# 2_MCU_schdoc.net
KiCad netlist of a schematic drawn in Altium Designer
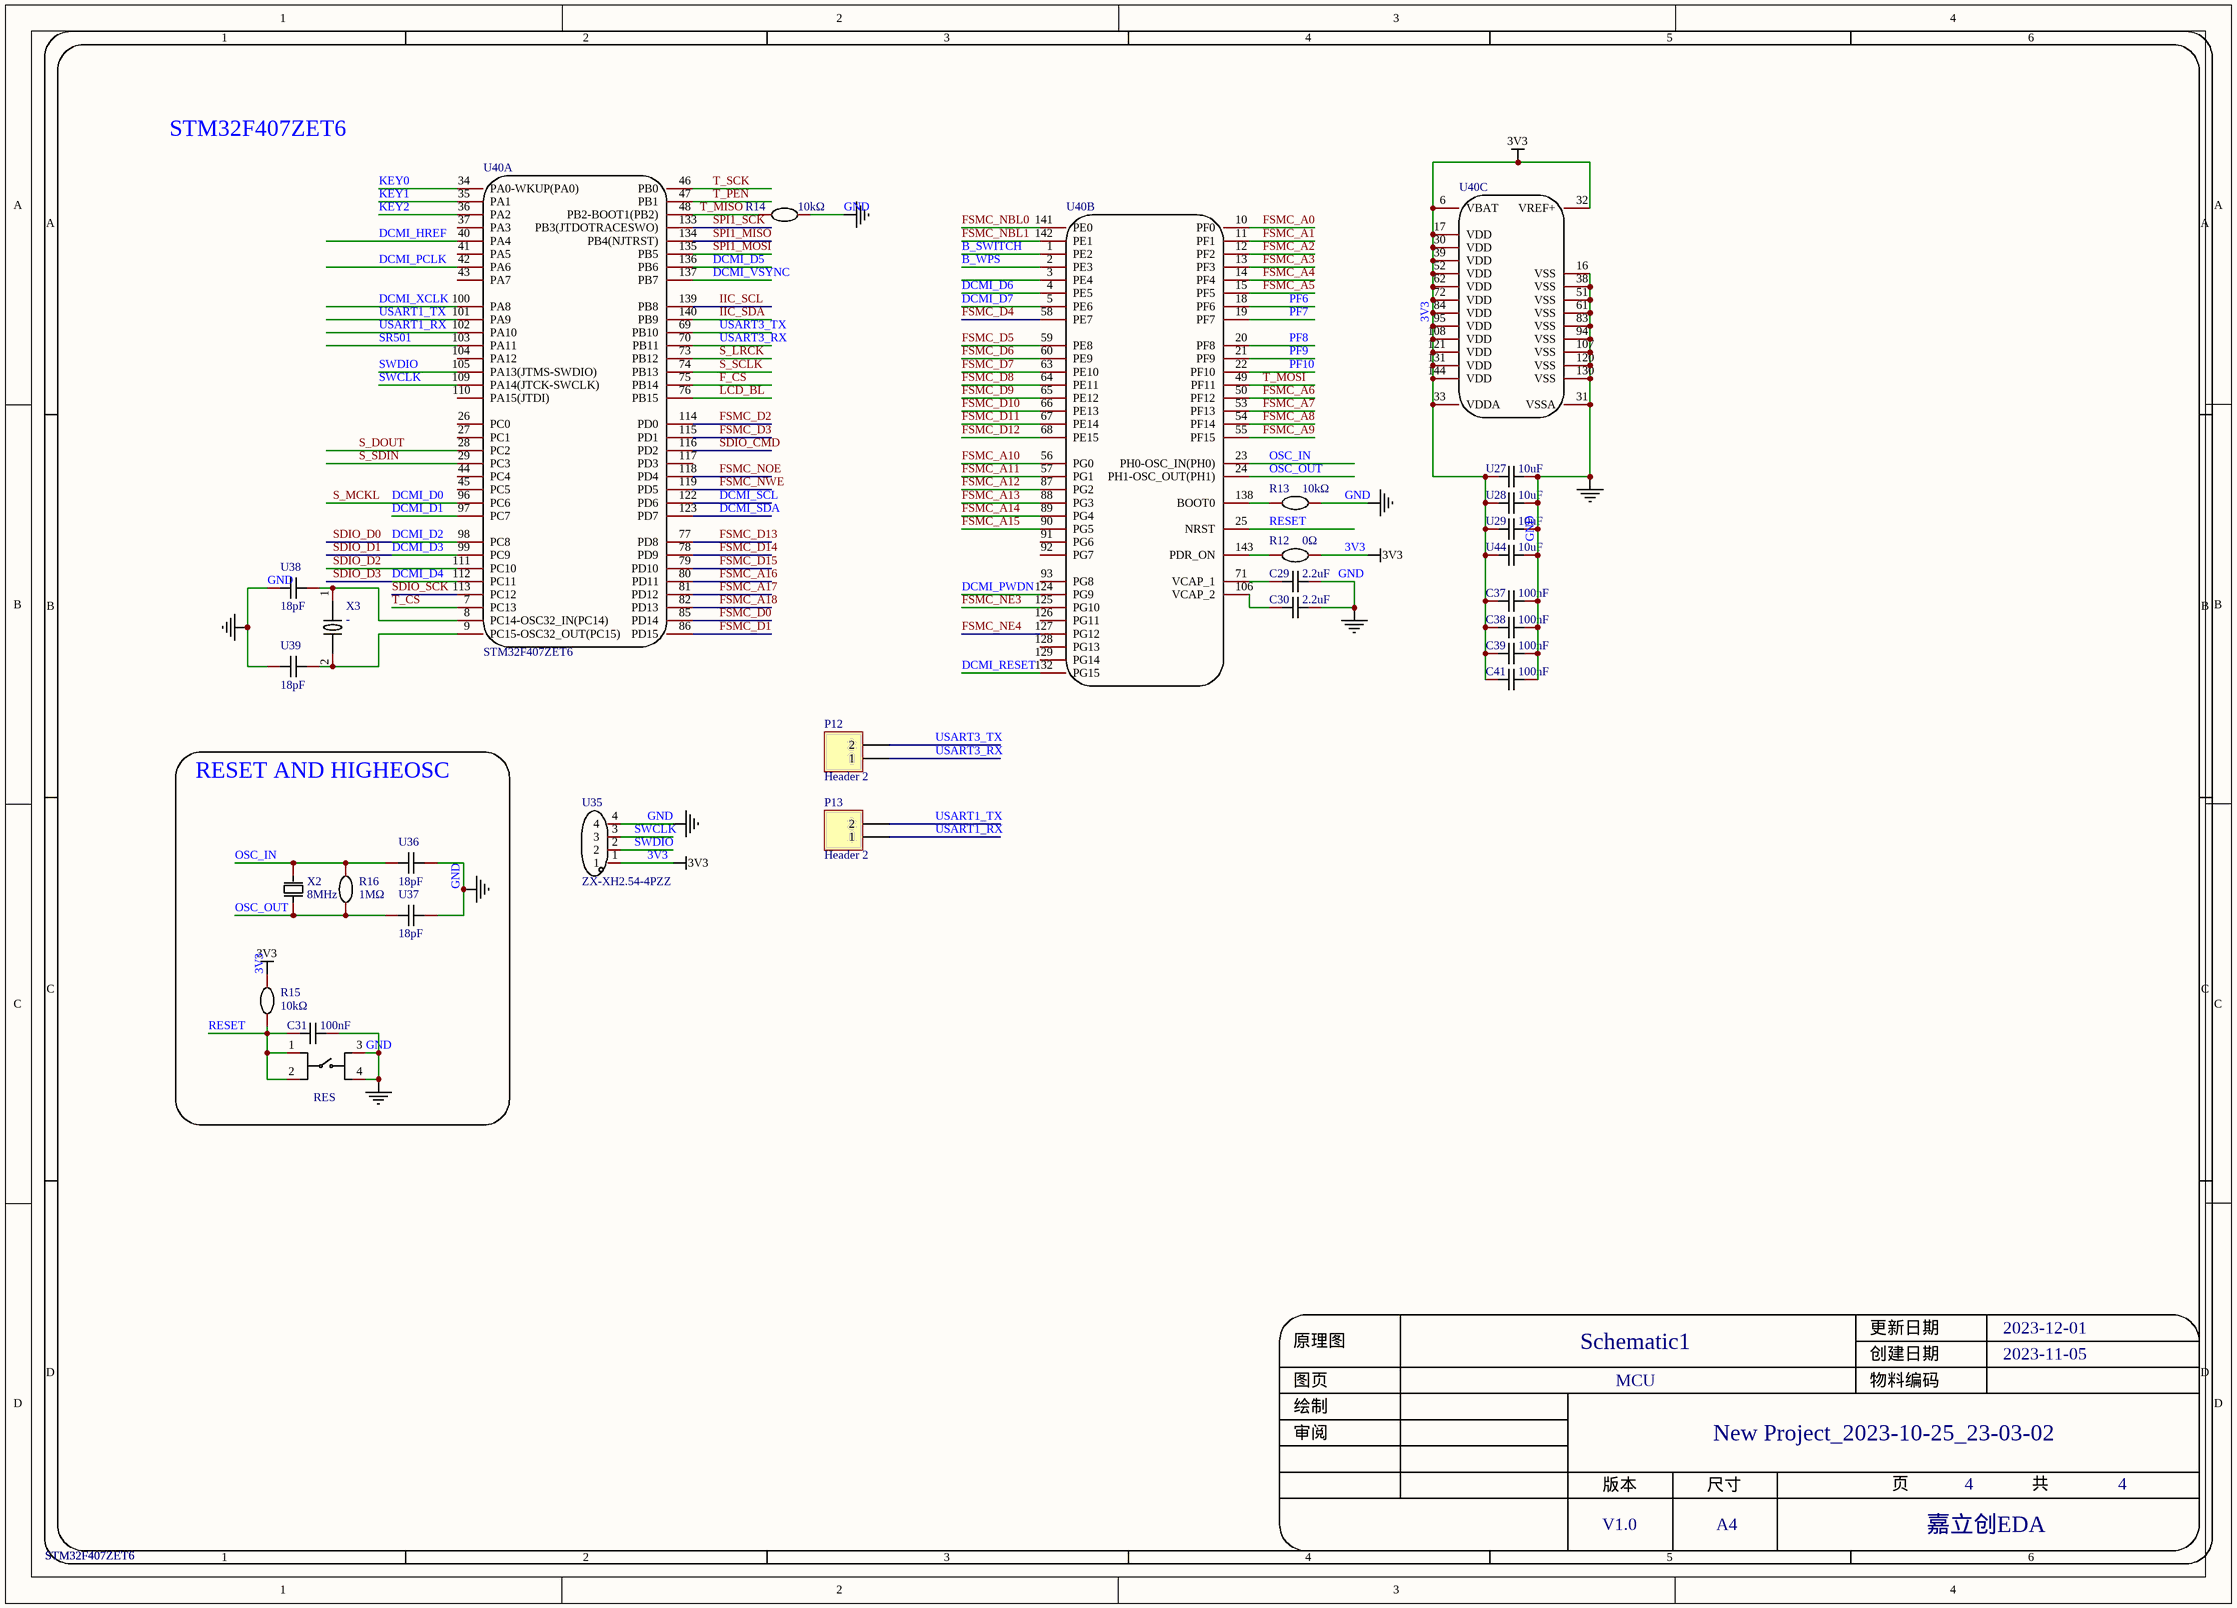
[diagram p0: 2_MCU.schdoc.schdoc]

(export (version "E")
  (design (tool "Eeschema 10.0.6"))
  (components
    (comp (ref "C29")
      (value "2.2uF")
      (footprint "C0603")
      (description "容值:2.2uF;精度:±10%;额定电压:10V;材质(温度系数):X6S;")
      (fields
        (field (name "NAME") "2.2uF")
        (field (name "MANUFACTURER") "TDK")
        (field (name "MANUFACTURER PART") "C1608X6S1A225K080AB")
      )
      (libsource (lib "altium-import") (part "root_0_C1608X6S1A225K080AB_"))
    )
    (comp (ref "C30")
      (value "2.2uF")
      (footprint "C0603")
      (description "容值:2.2uF;精度:±10%;额定电压:10V;材质(温度系数):X6S;")
      (fields
        (field (name "NAME") "2.2uF")
        (field (name "MANUFACTURER") "TDK")
        (field (name "MANUFACTURER PART") "C1608X6S1A225K080AB")
      )
      (libsource (lib "altium-import") (part "root_0_C1608X6S1A225K080AB_"))
    )
    (comp (ref "C31")
      (value "100nF")
      (footprint "C0603")
      (description "容值:100nF;精度:±20%;额定电压:50V;材质(温度系数):X8R;")
      (fields
        (field (name "NAME") "100nF")
        (field (name "MANUFACTURER") "TDK")
        (field (name "MANUFACTURER PART") "CGA3E3X8R1H104M080AE")
      )
      (libsource (lib "altium-import") (part "root_0_CGA3E3X8R1H104M080AE_"))
    )
    (comp (ref "C37")
      (value "100nF")
      (footprint "C0603")
      (description "容值:100nF;精度:±20%;额定电压:50V;材质(温度系数):X8R;")
      (fields
        (field (name "NAME") "100nF")
        (field (name "MANUFACTURER") "TDK")
        (field (name "MANUFACTURER PART") "CGA3E3X8R1H104M080AE")
      )
      (libsource (lib "altium-import") (part "root_0_CGA3E3X8R1H104M080AE_"))
    )
    (comp (ref "C38")
      (value "100nF")
      (footprint "C0603")
      (description "容值:100nF;精度:±20%;额定电压:50V;材质(温度系数):X8R;")
      (fields
        (field (name "NAME") "100nF")
        (field (name "MANUFACTURER") "TDK")
        (field (name "MANUFACTURER PART") "CGA3E3X8R1H104M080AE")
      )
      (libsource (lib "altium-import") (part "root_0_CGA3E3X8R1H104M080AE_"))
    )
    (comp (ref "C39")
      (value "100nF")
      (footprint "C0603")
      (description "容值:100nF;精度:±20%;额定电压:50V;材质(温度系数):X8R;")
      (fields
        (field (name "NAME") "100nF")
        (field (name "MANUFACTURER") "TDK")
        (field (name "MANUFACTURER PART") "CGA3E3X8R1H104M080AE")
      )
      (libsource (lib "altium-import") (part "root_0_CGA3E3X8R1H104M080AE_"))
    )
    (comp (ref "C41")
      (value "100nF")
      (footprint "C0603")
      (description "容值:100nF;精度:±20%;额定电压:50V;材质(温度系数):X8R;")
      (fields
        (field (name "NAME") "100nF")
        (field (name "MANUFACTURER") "TDK")
        (field (name "MANUFACTURER PART") "CGA3E3X8R1H104M080AE")
      )
      (libsource (lib "altium-import") (part "root_0_CGA3E3X8R1H104M080AE_"))
    )
    (comp (ref "P12")
      (value "Header 2")
      (footprint "HDR1X2")
      (description "Header, 2-Pin")
      (fields (field (name "PUBLISHER") "Altium Limited"))
      (libsource (lib "Miscellaneous Connectors") (part "Header 2"))
    )
    (comp (ref "P13")
      (value "Header 2")
      (footprint "HDR1X2")
      (description "Header, 2-Pin")
      (fields (field (name "PUBLISHER") "Altium Limited"))
      (libsource (lib "Miscellaneous Connectors") (part "Header 2"))
    )
    (comp (ref "R12")
      (value "0Ω")
      (footprint "R0603")
      (description "电阻类型:厚膜电阻;阻值:0Ω;精度:-;功率:100mW;")
      (fields
        (field (name "NAME") "0Ω")
        (field (name "MANUFACTURER") "YAGEO(国巨)")
        (field (name "MANUFACTURER PART") "RC0603JR-130RL")
      )
      (libsource (lib "altium-import") (part "root_0_RC0603JR-130RL_"))
    )
    (comp (ref "R13")
      (value "10kΩ")
      (footprint "R0603")
      (description "阻值:10kΩ;精度:±5%;")
      (fields
        (field (name "NAME") "10kΩ")
        (field (name "MANUFACTURER") "VO(翔胜)")
        (field (name "MANUFACTURER PART") "SCR0603J10K")
      )
      (libsource (lib "altium-import") (part "root_0_SCR0603J10K_"))
    )
    (comp (ref "R14")
      (value "10kΩ")
      (footprint "R0603")
      (description "阻值:10kΩ;精度:±5%;")
      (fields
        (field (name "NAME") "10kΩ")
        (field (name "MANUFACTURER") "VO(翔胜)")
        (field (name "MANUFACTURER PART") "SCR0603J10K")
      )
      (libsource (lib "altium-import") (part "root_0_SCR0603J10K_"))
    )
    (comp (ref "R15")
      (value "10kΩ")
      (footprint "R0603")
      (description "阻值:10kΩ;精度:±5%;")
      (fields
        (field (name "NAME") "10kΩ")
        (field (name "MANUFACTURER") "VO(翔胜)")
        (field (name "MANUFACTURER PART") "SCR0603J10K")
      )
      (libsource (lib "altium-import") (part "root_1_SCR0603J10K_"))
    )
    (comp (ref "R16")
      (value "1MΩ")
      (footprint "R0603")
      (description "电阻类型:厚膜电阻;阻值:1MΩ;精度:±5%;功率:100mW;")
      (fields
        (field (name "NAME") "1MΩ")
        (field (name "MANUFACTURER") "VISHAY(威世)")
        (field (name "MANUFACTURER PART") "CRCW06031M00JNEAC")
      )
      (libsource (lib "altium-import") (part "root_1_CRCW06031M00JNEAC_"))
    )
    (comp (ref "RES")
      (value "K2-6639SP-C4SC-04")
      (footprint "KEY-SMD_4P-L6.0-W6.0-P3.90-LS10.0")
      (fields (field (name "MANUFACTURER") "韩国韩荣"))
      (libsource (lib "altium-import") (part "root_0_K2-6639SP-C4SC-04_"))
    )
    (comp (ref "U27")
      (value "10uF")
      (footprint "C0603")
      (description "容值:10uF;精度:±20%;额定电压:16V;材质(温度系数):JB;")
      (fields
        (field (name "NAME") "10uF")
        (field (name "MANUFACTURER") "TDK")
        (field (name "MANUFACTURER PART") "C1608JB1C106M080AB")
      )
      (libsource (lib "altium-import") (part "root_0_C1608JB1C106M080AB_"))
    )
    (comp (ref "U28")
      (value "10uF")
      (footprint "C0603")
      (description "容值:10uF;精度:±20%;额定电压:16V;材质(温度系数):JB;")
      (fields
        (field (name "NAME") "10uF")
        (field (name "MANUFACTURER") "TDK")
        (field (name "MANUFACTURER PART") "C1608JB1C106M080AB")
      )
      (libsource (lib "altium-import") (part "root_0_C1608JB1C106M080AB_"))
    )
    (comp (ref "U29")
      (value "10uF")
      (footprint "C0603")
      (description "容值:10uF;精度:±20%;额定电压:16V;材质(温度系数):JB;")
      (fields
        (field (name "NAME") "10uF")
        (field (name "MANUFACTURER") "TDK")
        (field (name "MANUFACTURER PART") "C1608JB1C106M080AB")
      )
      (libsource (lib "altium-import") (part "root_0_C1608JB1C106M080AB_"))
    )
    (comp (ref "U35")
      (value "ZX-XH2.54-4PZZ")
      (footprint "CONN-TH_4P-P2.50_4PIN")
      (fields (field (name "NAME") "ZX-XH2.54-4PZZ") (field (name "MANUFACTURER") "Megastar(兆星)"))
      (libsource (lib "altium-import") (part "root_2_ZX-XH2.54-4PZZ_"))
    )
    (comp (ref "U36")
      (value "18pF")
      (footprint "C0603")
      (description "容值:18pF;精度:±5%;额定电压:100V;材质(温度系数):CH;")
      (fields
        (field (name "NAME") "18pF")
        (field (name "MANUFACTURER") "TDK")
        (field (name "MANUFACTURER PART") "C1608CH2A180J080AA")
      )
      (libsource (lib "altium-import") (part "root_0_C1608CH2A180J080AA_"))
    )
    (comp (ref "U37")
      (value "18pF")
      (footprint "C0603")
      (description "容值:18pF;精度:±5%;额定电压:100V;材质(温度系数):CH;")
      (fields
        (field (name "NAME") "18pF")
        (field (name "MANUFACTURER") "TDK")
        (field (name "MANUFACTURER PART") "C1608CH2A180J080AA")
      )
      (libsource (lib "altium-import") (part "root_0_C1608CH2A180J080AA_"))
    )
    (comp (ref "U38")
      (value "18pF")
      (footprint "C0603")
      (description "容值:18pF;精度:±5%;额定电压:100V;材质(温度系数):CH;")
      (fields
        (field (name "NAME") "18pF")
        (field (name "MANUFACTURER") "TDK")
        (field (name "MANUFACTURER PART") "C1608CH2A180J080AA")
      )
      (libsource (lib "altium-import") (part "root_0_C1608CH2A180J080AA_"))
    )
    (comp (ref "U39")
      (value "18pF")
      (footprint "C0603")
      (description "容值:18pF;精度:±5%;额定电压:100V;材质(温度系数):CH;")
      (fields
        (field (name "NAME") "18pF")
        (field (name "MANUFACTURER") "TDK")
        (field (name "MANUFACTURER PART") "C1608CH2A180J080AA")
      )
      (libsource (lib "altium-import") (part "root_0_C1608CH2A180J080AA_"))
    )
    (comp (ref "U40")
      (value "STM32F407ZET6")
      (footprint "LQFP-144_L20.0-W20.0-P0.50-LS22.0-BL")
      (fields (field (name "NAME") "STM32F407ZET6") (field (name "MANUFACTURER") "ST(意法半导体)"))
      (libsource (lib "altium-import") (part "root_0_STM32F407ZET6_"))
    )
    (comp (ref "U44")
      (value "10uF")
      (footprint "C0603")
      (description "容值:10uF;精度:±20%;额定电压:16V;材质(温度系数):JB;")
      (fields
        (field (name "NAME") "10uF")
        (field (name "MANUFACTURER") "TDK")
        (field (name "MANUFACTURER PART") "C1608JB1C106M080AB")
      )
      (libsource (lib "altium-import") (part "root_0_C1608JB1C106M080AB_"))
    )
    (comp (ref "X2")
      (value "8MHz")
      (footprint "OSC-SMD_L5.0-W3.2")
      (description "频率:8MHz;频率公差:±30ppm;负载电容:20pF;")
      (fields
        (field (name "NAME") "8MHz")
        (field (name "MANUFACTURER") "TAE(雅晶鑫)")
        (field (name "MANUFACTURER PART") "TAXM8M2QLFCDT1T")
      )
      (libsource (lib "altium-import") (part "root_1_TAXM8M2QLFCDT1T_"))
    )
    (comp (ref "X3")
      (value "-")
      (footprint "OSC-SMD_2P-L1.6-W1.0")
      (description "频率:-;负载电容:-;")
      (fields
        (field (name "NAME") "-")
        (field (name "MANUFACTURER") "RIVER(大河)")
        (field (name "MANUFACTURER PART") "TFX-04-32.768K")
      )
      (libsource (lib "altium-import") (part "root_3_TFX-04-32.768K_"))
    )
  )
  (nets
    (net (code "1") (name "/B_SWITCH") (class "Default")
      (node (ref "U40") (pin "1") (pinfunction "PE2_1") (pintype "passive"))
    )
    (net (code "2") (name "/B_WPS") (class "Default")
      (node (ref "U40") (pin "2") (pinfunction "PE3_2") (pintype "passive"))
    )
    (net (code "3") (name "/DCMI_D0") (class "Default")
      (node (ref "U40") (pin "96") (pinfunction "PC6_96") (pintype "passive"))
    )
    (net (code "4") (name "/DCMI_D1") (class "Default")
      (node (ref "U40") (pin "97") (pinfunction "PC7_97") (pintype "passive"))
    )
    (net (code "5") (name "/DCMI_D2") (class "Default")
      (node (ref "U40") (pin "98") (pinfunction "PC8_98") (pintype "passive"))
    )
    (net (code "6") (name "/DCMI_D3") (class "Default")
      (node (ref "U40") (pin "99") (pinfunction "PC9_99") (pintype "passive"))
    )
    (net (code "7") (name "/DCMI_D4") (class "Default")
      (node (ref "U40") (pin "112") (pinfunction "PC11_112") (pintype "passive"))
    )
    (net (code "8") (name "/DCMI_D5") (class "Default")
      (node (ref "U40") (pin "136") (pinfunction "PB6_136") (pintype "passive"))
    )
    (net (code "9") (name "/DCMI_D6") (class "Default")
      (node (ref "U40") (pin "4") (pinfunction "PE5_4") (pintype "passive"))
    )
    (net (code "10") (name "/DCMI_D7") (class "Default")
      (node (ref "U40") (pin "5") (pinfunction "PE6_5") (pintype "passive"))
    )
    (net (code "11") (name "/DCMI_HREF") (class "Default")
      (node (ref "U40") (pin "40") (pinfunction "PA4_40") (pintype "passive"))
    )
    (net (code "12") (name "/DCMI_PCLK") (class "Default")
      (node (ref "U40") (pin "42") (pinfunction "PA6_42") (pintype "passive"))
    )
    (net (code "13") (name "/DCMI_PWDN") (class "Default")
      (node (ref "U40") (pin "124") (pinfunction "PG9_124") (pintype "passive"))
    )
    (net (code "14") (name "/DCMI_RESET") (class "Default")
      (node (ref "U40") (pin "132") (pinfunction "PG15_132") (pintype "passive"))
    )
    (net (code "15") (name "/DCMI_SCL") (class "Default")
      (node (ref "U40") (pin "122") (pinfunction "PD6_122") (pintype "passive"))
    )
    (net (code "16") (name "/DCMI_SDA") (class "Default")
      (node (ref "U40") (pin "123") (pinfunction "PD7_123") (pintype "passive"))
    )
    (net (code "17") (name "/DCMI_VSYNC") (class "Default")
      (node (ref "U40") (pin "137") (pinfunction "PB7_137") (pintype "passive"))
    )
    (net (code "18") (name "/DCMI_XCLK") (class "Default")
      (node (ref "U40") (pin "100") (pinfunction "PA8_100") (pintype "passive"))
    )
    (net (code "19") (name "/FSMC_A0") (class "Default")
      (node (ref "U40") (pin "10") (pinfunction "PF0_10") (pintype "passive"))
    )
    (net (code "20") (name "/FSMC_A1") (class "Default")
      (node (ref "U40") (pin "11") (pinfunction "PF1_11") (pintype "passive"))
    )
    (net (code "21") (name "/FSMC_A2") (class "Default")
      (node (ref "U40") (pin "12") (pinfunction "PF2_12") (pintype "passive"))
    )
    (net (code "22") (name "/FSMC_A3") (class "Default")
      (node (ref "U40") (pin "13") (pinfunction "PF3_13") (pintype "passive"))
    )
    (net (code "23") (name "/FSMC_A4") (class "Default")
      (node (ref "U40") (pin "14") (pinfunction "PF4_14") (pintype "passive"))
    )
    (net (code "24") (name "/FSMC_A5") (class "Default")
      (node (ref "U40") (pin "15") (pinfunction "PF5_15") (pintype "passive"))
    )
    (net (code "25") (name "/FSMC_A6") (class "Default")
      (node (ref "U40") (pin "50") (pinfunction "PF12_50") (pintype "passive"))
    )
    (net (code "26") (name "/FSMC_A7") (class "Default")
      (node (ref "U40") (pin "53") (pinfunction "PF13_53") (pintype "passive"))
    )
    (net (code "27") (name "/FSMC_A8") (class "Default")
      (node (ref "U40") (pin "54") (pinfunction "PF14_54") (pintype "passive"))
    )
    (net (code "28") (name "/FSMC_A9") (class "Default")
      (node (ref "U40") (pin "55") (pinfunction "PF15_55") (pintype "passive"))
    )
    (net (code "29") (name "/FSMC_A10") (class "Default")
      (node (ref "U40") (pin "56") (pinfunction "PG0_56") (pintype "passive"))
    )
    (net (code "30") (name "/FSMC_A11") (class "Default")
      (node (ref "U40") (pin "57") (pinfunction "PG1_57") (pintype "passive"))
    )
    (net (code "31") (name "/FSMC_A12") (class "Default")
      (node (ref "U40") (pin "87") (pinfunction "PG2_87") (pintype "passive"))
    )
    (net (code "32") (name "/FSMC_A13") (class "Default")
      (node (ref "U40") (pin "88") (pinfunction "PG3_88") (pintype "passive"))
    )
    (net (code "33") (name "/FSMC_A14") (class "Default")
      (node (ref "U40") (pin "89") (pinfunction "PG4_89") (pintype "passive"))
    )
    (net (code "34") (name "/FSMC_A15") (class "Default")
      (node (ref "U40") (pin "90") (pinfunction "PG5_90") (pintype "passive"))
    )
    (net (code "35") (name "/FSMC_A16") (class "Default")
      (node (ref "U40") (pin "80") (pinfunction "PD11_80") (pintype "passive"))
    )
    (net (code "36") (name "/FSMC_A17") (class "Default")
      (node (ref "U40") (pin "81") (pinfunction "PD12_81") (pintype "passive"))
    )
    (net (code "37") (name "/FSMC_A18") (class "Default")
      (node (ref "U40") (pin "82") (pinfunction "PD13_82") (pintype "passive"))
    )
    (net (code "38") (name "/FSMC_D0") (class "Default")
      (node (ref "U40") (pin "85") (pinfunction "PD14_85") (pintype "passive"))
    )
    (net (code "39") (name "/FSMC_D1") (class "Default")
      (node (ref "U40") (pin "86") (pinfunction "PD15_86") (pintype "passive"))
    )
    (net (code "40") (name "/FSMC_D2") (class "Default")
      (node (ref "U40") (pin "114") (pinfunction "PD0_114") (pintype "passive"))
    )
    (net (code "41") (name "/FSMC_D3") (class "Default")
      (node (ref "U40") (pin "115") (pinfunction "PD1_115") (pintype "passive"))
    )
    (net (code "42") (name "/FSMC_D4") (class "Default")
      (node (ref "U40") (pin "58") (pinfunction "PE7_58") (pintype "passive"))
    )
    (net (code "43") (name "/FSMC_D5") (class "Default")
      (node (ref "U40") (pin "59") (pinfunction "PE8_59") (pintype "passive"))
    )
    (net (code "44") (name "/FSMC_D6") (class "Default")
      (node (ref "U40") (pin "60") (pinfunction "PE9_60") (pintype "passive"))
    )
    (net (code "45") (name "/FSMC_D7") (class "Default")
      (node (ref "U40") (pin "63") (pinfunction "PE10_63") (pintype "passive"))
    )
    (net (code "46") (name "/FSMC_D8") (class "Default")
      (node (ref "U40") (pin "64") (pinfunction "PE11_64") (pintype "passive"))
    )
    (net (code "47") (name "/FSMC_D9") (class "Default")
      (node (ref "U40") (pin "65") (pinfunction "PE12_65") (pintype "passive"))
    )
    (net (code "48") (name "/FSMC_D10") (class "Default")
      (node (ref "U40") (pin "66") (pinfunction "PE13_66") (pintype "passive"))
    )
    (net (code "49") (name "/FSMC_D11") (class "Default")
      (node (ref "U40") (pin "67") (pinfunction "PE14_67") (pintype "passive"))
    )
    (net (code "50") (name "/FSMC_D12") (class "Default")
      (node (ref "U40") (pin "68") (pinfunction "PE15_68") (pintype "passive"))
    )
    (net (code "51") (name "/FSMC_D13") (class "Default")
      (node (ref "U40") (pin "77") (pinfunction "PD8_77") (pintype "passive"))
    )
    (net (code "52") (name "/FSMC_D14") (class "Default")
      (node (ref "U40") (pin "78") (pinfunction "PD9_78") (pintype "passive"))
    )
    (net (code "53") (name "/FSMC_D15") (class "Default")
      (node (ref "U40") (pin "79") (pinfunction "PD10_79") (pintype "passive"))
    )
    (net (code "54") (name "/FSMC_NBL0") (class "Default")
      (node (ref "U40") (pin "141") (pinfunction "PE0_141") (pintype "passive"))
    )
    (net (code "55") (name "/FSMC_NBL1") (class "Default")
      (node (ref "U40") (pin "142") (pinfunction "PE1_142") (pintype "passive"))
    )
    (net (code "56") (name "/FSMC_NE3") (class "Default")
      (node (ref "U40") (pin "125") (pinfunction "PG10_125") (pintype "passive"))
    )
    (net (code "57") (name "/FSMC_NE4") (class "Default")
      (node (ref "U40") (pin "127") (pinfunction "PG12_127") (pintype "passive"))
    )
    (net (code "58") (name "/FSMC_NOE") (class "Default")
      (node (ref "U40") (pin "118") (pinfunction "PD4_118") (pintype "passive"))
    )
    (net (code "59") (name "/FSMC_NWE") (class "Default")
      (node (ref "U40") (pin "119") (pinfunction "PD5_119") (pintype "passive"))
    )
    (net (code "60") (name "/F_CS") (class "Default")
      (node (ref "U40") (pin "75") (pinfunction "PB14_75") (pintype "passive"))
    )
    (net (code "61") (name "/GND") (class "Default")
      (node (ref "C29") (pin "2") (pinfunction "2_2") (pintype "passive"))
      (node (ref "C30") (pin "2") (pinfunction "2_2") (pintype "passive"))
      (node (ref "C31") (pin "2") (pinfunction "2_2") (pintype "passive"))
      (node (ref "C37") (pin "2") (pinfunction "2_2") (pintype "passive"))
      (node (ref "C38") (pin "2") (pinfunction "2_2") (pintype "passive"))
      (node (ref "C39") (pin "2") (pinfunction "2_2") (pintype "passive"))
      (node (ref "C41") (pin "2") (pinfunction "2_2") (pintype "passive"))
      (node (ref "R13") (pin "2") (pinfunction "2_2") (pintype "passive"))
      (node (ref "R14") (pin "2") (pinfunction "2_2") (pintype "passive"))
      (node (ref "RES") (pin "3") (pinfunction "3_3") (pintype "passive"))
      (node (ref "RES") (pin "4") (pinfunction "4_4") (pintype "passive"))
      (node (ref "U27") (pin "2") (pinfunction "2_2") (pintype "passive"))
      (node (ref "U28") (pin "2") (pinfunction "2_2") (pintype "passive"))
      (node (ref "U29") (pin "2") (pinfunction "2_2") (pintype "passive"))
      (node (ref "U35") (pin "4") (pinfunction "4_4") (pintype "passive"))
      (node (ref "U36") (pin "2") (pinfunction "2_2") (pintype "passive"))
      (node (ref "U37") (pin "2") (pinfunction "2_2") (pintype "passive"))
      (node (ref "U38") (pin "1") (pinfunction "1_1") (pintype "passive"))
      (node (ref "U39") (pin "1") (pinfunction "1_1") (pintype "passive"))
      (node (ref "U40") (pin "107") (pinfunction "VSS_107") (pintype "passive"))
      (node (ref "U40") (pin "120") (pinfunction "VSS_120") (pintype "passive"))
      (node (ref "U40") (pin "130") (pinfunction "VSS_130") (pintype "passive"))
      (node (ref "U40") (pin "16") (pinfunction "VSS_16") (pintype "passive"))
      (node (ref "U40") (pin "31") (pinfunction "VSSA_31") (pintype "passive"))
      (node (ref "U40") (pin "38") (pinfunction "VSS_38") (pintype "passive"))
      (node (ref "U40") (pin "51") (pinfunction "VSS_51") (pintype "passive"))
      (node (ref "U40") (pin "61") (pinfunction "VSS_61") (pintype "passive"))
      (node (ref "U40") (pin "83") (pinfunction "VSS_83") (pintype "passive"))
      (node (ref "U40") (pin "94") (pinfunction "VSS_94") (pintype "passive"))
      (node (ref "U44") (pin "2") (pinfunction "2_2") (pintype "passive"))
    )
    (net (code "62") (name "/IIC_SCL") (class "Default")
      (node (ref "U40") (pin "139") (pinfunction "PB8_139") (pintype "passive"))
    )
    (net (code "63") (name "/IIC_SDA") (class "Default")
      (node (ref "U40") (pin "140") (pinfunction "PB9_140") (pintype "passive"))
    )
    (net (code "64") (name "/KEY0") (class "Default")
      (node (ref "U40") (pin "34") (pinfunction "PA0-WKUP(PA0)_34") (pintype "passive"))
    )
    (net (code "65") (name "/KEY1") (class "Default")
      (node (ref "U40") (pin "35") (pinfunction "PA1_35") (pintype "passive"))
    )
    (net (code "66") (name "/KEY2") (class "Default")
      (node (ref "U40") (pin "36") (pinfunction "PA2_36") (pintype "passive"))
    )
    (net (code "67") (name "/LCD_BL") (class "Default")
      (node (ref "U40") (pin "76") (pinfunction "PB15_76") (pintype "passive"))
    )
    (net (code "68") (name "/OSC_IN") (class "Default")
      (node (ref "R16") (pin "2") (pinfunction "2_2") (pintype "passive"))
      (node (ref "U36") (pin "1") (pinfunction "1_1") (pintype "passive"))
      (node (ref "U40") (pin "23") (pinfunction "PH0-OSC_IN(PH0)_23") (pintype "passive"))
      (node (ref "X2") (pin "2") (pinfunction "OSC2_2") (pintype "passive"))
    )
    (net (code "69") (name "/OSC_OUT") (class "Default")
      (node (ref "R16") (pin "1") (pinfunction "1_1") (pintype "passive"))
      (node (ref "U37") (pin "1") (pinfunction "1_1") (pintype "passive"))
      (node (ref "U40") (pin "24") (pinfunction "PH1-OSC_OUT(PH1)_24") (pintype "passive"))
      (node (ref "X2") (pin "1") (pinfunction "OSC1_1") (pintype "passive"))
    )
    (net (code "70") (name "/PF6") (class "Default")
      (node (ref "U40") (pin "18") (pinfunction "PF6_18") (pintype "passive"))
    )
    (net (code "71") (name "/PF7") (class "Default")
      (node (ref "U40") (pin "19") (pinfunction "PF7_19") (pintype "passive"))
    )
    (net (code "72") (name "/PF8") (class "Default")
      (node (ref "U40") (pin "20") (pinfunction "PF8_20") (pintype "passive"))
    )
    (net (code "73") (name "/PF9") (class "Default")
      (node (ref "U40") (pin "21") (pinfunction "PF9_21") (pintype "passive"))
    )
    (net (code "74") (name "/PF10") (class "Default")
      (node (ref "U40") (pin "22") (pinfunction "PF10_22") (pintype "passive"))
    )
    (net (code "75") (name "/RESET") (class "Default")
      (node (ref "C31") (pin "1") (pinfunction "1_1") (pintype "passive"))
      (node (ref "R15") (pin "1") (pinfunction "1_1") (pintype "passive"))
      (node (ref "RES") (pin "1") (pinfunction "1_1") (pintype "passive"))
      (node (ref "RES") (pin "2") (pinfunction "2_2") (pintype "passive"))
      (node (ref "U40") (pin "25") (pinfunction "NRST_25") (pintype "passive"))
    )
    (net (code "76") (name "/SDIO_CMD") (class "Default")
      (node (ref "U40") (pin "116") (pinfunction "PD2_116") (pintype "passive"))
    )
    (net (code "77") (name "/SDIO_D2") (class "Default")
      (node (ref "U40") (pin "111") (pinfunction "PC10_111") (pintype "passive"))
    )
    (net (code "78") (name "/SDIO_SCK") (class "Default")
      (node (ref "U40") (pin "113") (pinfunction "PC12_113") (pintype "passive"))
    )
    (net (code "79") (name "/SPI1_MISO") (class "Default")
      (node (ref "U40") (pin "134") (pinfunction "PB4(NJTRST)_134") (pintype "passive"))
    )
    (net (code "80") (name "/SPI1_MOSI") (class "Default")
      (node (ref "U40") (pin "135") (pinfunction "PB5_135") (pintype "passive"))
    )
    (net (code "81") (name "/SPI1_SCK") (class "Default")
      (node (ref "U40") (pin "133") (pinfunction "PB3(JTDOTRACESWO)_133") (pintype "passive"))
    )
    (net (code "82") (name "/SR501") (class "Default")
      (node (ref "U40") (pin "103") (pinfunction "PA11_103") (pintype "passive"))
    )
    (net (code "83") (name "/SWCLK") (class "Default")
      (node (ref "U35") (pin "3") (pinfunction "3_3") (pintype "passive"))
      (node (ref "U40") (pin "109") (pinfunction "PA14(JTCK-SWCLK)_109") (pintype "passive"))
    )
    (net (code "84") (name "/SWDIO") (class "Default")
      (node (ref "U35") (pin "2") (pinfunction "2_2") (pintype "passive"))
      (node (ref "U40") (pin "105") (pinfunction "PA13(JTMS-SWDIO)_105") (pintype "passive"))
    )
    (net (code "85") (name "/S_DOUT") (class "Default")
      (node (ref "U40") (pin "28") (pinfunction "PC2_28") (pintype "passive"))
    )
    (net (code "86") (name "/S_LRCK") (class "Default")
      (node (ref "U40") (pin "73") (pinfunction "PB12_73") (pintype "passive"))
    )
    (net (code "87") (name "/S_SCLK") (class "Default")
      (node (ref "U40") (pin "74") (pinfunction "PB13_74") (pintype "passive"))
    )
    (net (code "88") (name "/S_SDIN") (class "Default")
      (node (ref "U40") (pin "29") (pinfunction "PC3_29") (pintype "passive"))
    )
    (net (code "89") (name "/T_CS") (class "Default")
      (node (ref "U40") (pin "7") (pinfunction "PC13_7") (pintype "passive"))
    )
    (net (code "90") (name "/T_MISO") (class "Default")
      (node (ref "R14") (pin "1") (pinfunction "1_1") (pintype "passive"))
      (node (ref "U40") (pin "48") (pinfunction "PB2-BOOT1(PB2)_48") (pintype "passive"))
    )
    (net (code "91") (name "/T_MOSI") (class "Default")
      (node (ref "U40") (pin "49") (pinfunction "PF11_49") (pintype "passive"))
    )
    (net (code "92") (name "/T_PEN") (class "Default")
      (node (ref "U40") (pin "47") (pinfunction "PB1_47") (pintype "passive"))
    )
    (net (code "93") (name "/T_SCK") (class "Default")
      (node (ref "U40") (pin "46") (pinfunction "PB0_46") (pintype "passive"))
    )
    (net (code "94") (name "/USART1_RX") (class "Default")
      (node (ref "P13") (pin "1") (pinfunction "1_1") (pintype "passive"))
      (node (ref "U40") (pin "102") (pinfunction "PA10_102") (pintype "passive"))
    )
    (net (code "95") (name "/USART1_TX") (class "Default")
      (node (ref "P13") (pin "2") (pinfunction "2_2") (pintype "passive"))
      (node (ref "U40") (pin "101") (pinfunction "PA9_101") (pintype "passive"))
    )
    (net (code "96") (name "/USART3_RX") (class "Default")
      (node (ref "P12") (pin "1") (pinfunction "1_1") (pintype "passive"))
      (node (ref "U40") (pin "70") (pinfunction "PB11_70") (pintype "passive"))
    )
    (net (code "97") (name "/USART3_TX") (class "Default")
      (node (ref "P12") (pin "2") (pinfunction "2_2") (pintype "passive"))
      (node (ref "U40") (pin "69") (pinfunction "PB10_69") (pintype "passive"))
    )
    (net (code "98") (name "3V3") (class "Default")
      (node (ref "C37") (pin "1") (pinfunction "1_1") (pintype "passive"))
      (node (ref "C38") (pin "1") (pinfunction "1_1") (pintype "passive"))
      (node (ref "C39") (pin "1") (pinfunction "1_1") (pintype "passive"))
      (node (ref "C41") (pin "1") (pinfunction "1_1") (pintype "passive"))
      (node (ref "R12") (pin "2") (pinfunction "2_2") (pintype "passive"))
      (node (ref "R15") (pin "2") (pinfunction "2_2") (pintype "passive"))
      (node (ref "U27") (pin "1") (pinfunction "1_1") (pintype "passive"))
      (node (ref "U28") (pin "1") (pinfunction "1_1") (pintype "passive"))
      (node (ref "U29") (pin "1") (pinfunction "1_1") (pintype "passive"))
      (node (ref "U35") (pin "1") (pinfunction "1_1") (pintype "passive"))
      (node (ref "U40") (pin "108") (pinfunction "VDD_108") (pintype "passive"))
      (node (ref "U40") (pin "121") (pinfunction "VDD_121") (pintype "passive"))
      (node (ref "U40") (pin "131") (pinfunction "VDD_131") (pintype "passive"))
      (node (ref "U40") (pin "144") (pinfunction "VDD_144") (pintype "passive"))
      (node (ref "U40") (pin "17") (pinfunction "VDD_17") (pintype "passive"))
      (node (ref "U40") (pin "30") (pinfunction "VDD_30") (pintype "passive"))
      (node (ref "U40") (pin "32") (pinfunction "VREF+_32") (pintype "passive"))
      (node (ref "U40") (pin "33") (pinfunction "VDDA_33") (pintype "passive"))
      (node (ref "U40") (pin "39") (pinfunction "VDD_39") (pintype "passive"))
      (node (ref "U40") (pin "52") (pinfunction "VDD_52") (pintype "passive"))
      (node (ref "U40") (pin "6") (pinfunction "VBAT_6") (pintype "passive"))
      (node (ref "U40") (pin "62") (pinfunction "VDD_62") (pintype "passive"))
      (node (ref "U40") (pin "72") (pinfunction "VDD_72") (pintype "passive"))
      (node (ref "U40") (pin "84") (pinfunction "VDD_84") (pintype "passive"))
      (node (ref "U40") (pin "95") (pinfunction "VDD_95") (pintype "passive"))
      (node (ref "U44") (pin "1") (pinfunction "1_1") (pintype "passive"))
    )
    (net (code "99") (name "Net-(U40A-PC14-OSC32_IN(PC14))") (class "Default")
      (node (ref "U38") (pin "2") (pinfunction "2_2") (pintype "passive"))
      (node (ref "U40") (pin "8") (pinfunction "PC14-OSC32_IN(PC14)_8") (pintype "passive"))
      (node (ref "X3") (pin "1") (pinfunction "1_1") (pintype "passive"))
    )
    (net (code "100") (name "Net-(U40A-PC15-OSC32_OUT(PC15))") (class "Default")
      (node (ref "U39") (pin "2") (pinfunction "2_2") (pintype "passive"))
      (node (ref "U40") (pin "9") (pinfunction "PC15-OSC32_OUT(PC15)_9") (pintype "passive"))
      (node (ref "X3") (pin "2") (pinfunction "2_2") (pintype "passive"))
    )
    (net (code "101") (name "Net-(U40B-BOOT0)") (class "Default")
      (node (ref "R13") (pin "1") (pinfunction "1_1") (pintype "passive"))
      (node (ref "U40") (pin "138") (pinfunction "BOOT0_138") (pintype "passive"))
    )
    (net (code "102") (name "Net-(U40B-PDR_ON)") (class "Default")
      (node (ref "R12") (pin "1") (pinfunction "1_1") (pintype "passive"))
      (node (ref "U40") (pin "143") (pinfunction "PDR_ON_143") (pintype "passive"))
    )
    (net (code "103") (name "Net-(U40B-VCAP_1)") (class "Default")
      (node (ref "C29") (pin "1") (pinfunction "1_1") (pintype "passive"))
      (node (ref "U40") (pin "71") (pinfunction "VCAP_1_71") (pintype "passive"))
    )
    (net (code "104") (name "Net-(U40B-VCAP_2)") (class "Default")
      (node (ref "C30") (pin "1") (pinfunction "1_1") (pintype "passive"))
      (node (ref "U40") (pin "106") (pinfunction "VCAP_2_106") (pintype "passive"))
    )
    (net (code "105") (name "unconnected-(U40A-PA3-Pad37)") (class "Default")
      (node (ref "U40") (pin "37") (pinfunction "PA3_37") (pintype "passive"))
    )
    (net (code "106") (name "unconnected-(U40A-PA5-Pad41)") (class "Default")
      (node (ref "U40") (pin "41") (pinfunction "PA5_41") (pintype "passive"))
    )
    (net (code "107") (name "unconnected-(U40A-PA7-Pad43)") (class "Default")
      (node (ref "U40") (pin "43") (pinfunction "PA7_43") (pintype "passive"))
    )
    (net (code "108") (name "unconnected-(U40A-PA12-Pad104)") (class "Default")
      (node (ref "U40") (pin "104") (pinfunction "PA12_104") (pintype "passive"))
    )
    (net (code "109") (name "unconnected-(U40A-PA15(JTDI)-Pad110)") (class "Default")
      (node (ref "U40") (pin "110") (pinfunction "PA15(JTDI)_110") (pintype "passive"))
    )
    (net (code "110") (name "unconnected-(U40A-PC0-Pad26)") (class "Default")
      (node (ref "U40") (pin "26") (pinfunction "PC0_26") (pintype "passive"))
    )
    (net (code "111") (name "unconnected-(U40A-PC1-Pad27)") (class "Default")
      (node (ref "U40") (pin "27") (pinfunction "PC1_27") (pintype "passive"))
    )
    (net (code "112") (name "unconnected-(U40A-PC4-Pad44)") (class "Default")
      (node (ref "U40") (pin "44") (pinfunction "PC4_44") (pintype "passive"))
    )
    (net (code "113") (name "unconnected-(U40A-PC5-Pad45)") (class "Default")
      (node (ref "U40") (pin "45") (pinfunction "PC5_45") (pintype "passive"))
    )
    (net (code "114") (name "unconnected-(U40A-PD3-Pad117)") (class "Default")
      (node (ref "U40") (pin "117") (pinfunction "PD3_117") (pintype "passive"))
    )
    (net (code "115") (name "unconnected-(U40B-PE4-Pad3)") (class "Default")
      (node (ref "U40") (pin "3") (pinfunction "PE4_3") (pintype "passive"))
    )
    (net (code "116") (name "unconnected-(U40B-PG6-Pad91)") (class "Default")
      (node (ref "U40") (pin "91") (pinfunction "PG6_91") (pintype "passive"))
    )
    (net (code "117") (name "unconnected-(U40B-PG7-Pad92)") (class "Default")
      (node (ref "U40") (pin "92") (pinfunction "PG7_92") (pintype "passive"))
    )
    (net (code "118") (name "unconnected-(U40B-PG8-Pad93)") (class "Default")
      (node (ref "U40") (pin "93") (pinfunction "PG8_93") (pintype "passive"))
    )
    (net (code "119") (name "unconnected-(U40B-PG11-Pad126)") (class "Default")
      (node (ref "U40") (pin "126") (pinfunction "PG11_126") (pintype "passive"))
    )
    (net (code "120") (name "unconnected-(U40B-PG13-Pad128)") (class "Default")
      (node (ref "U40") (pin "128") (pinfunction "PG13_128") (pintype "passive"))
    )
    (net (code "121") (name "unconnected-(U40B-PG14-Pad129)") (class "Default")
      (node (ref "U40") (pin "129") (pinfunction "PG14_129") (pintype "passive"))
    )
  )
)
